# 06_MOV16_DestinationRegister.net
KiCad netlist of a schematic drawn in EAGLE
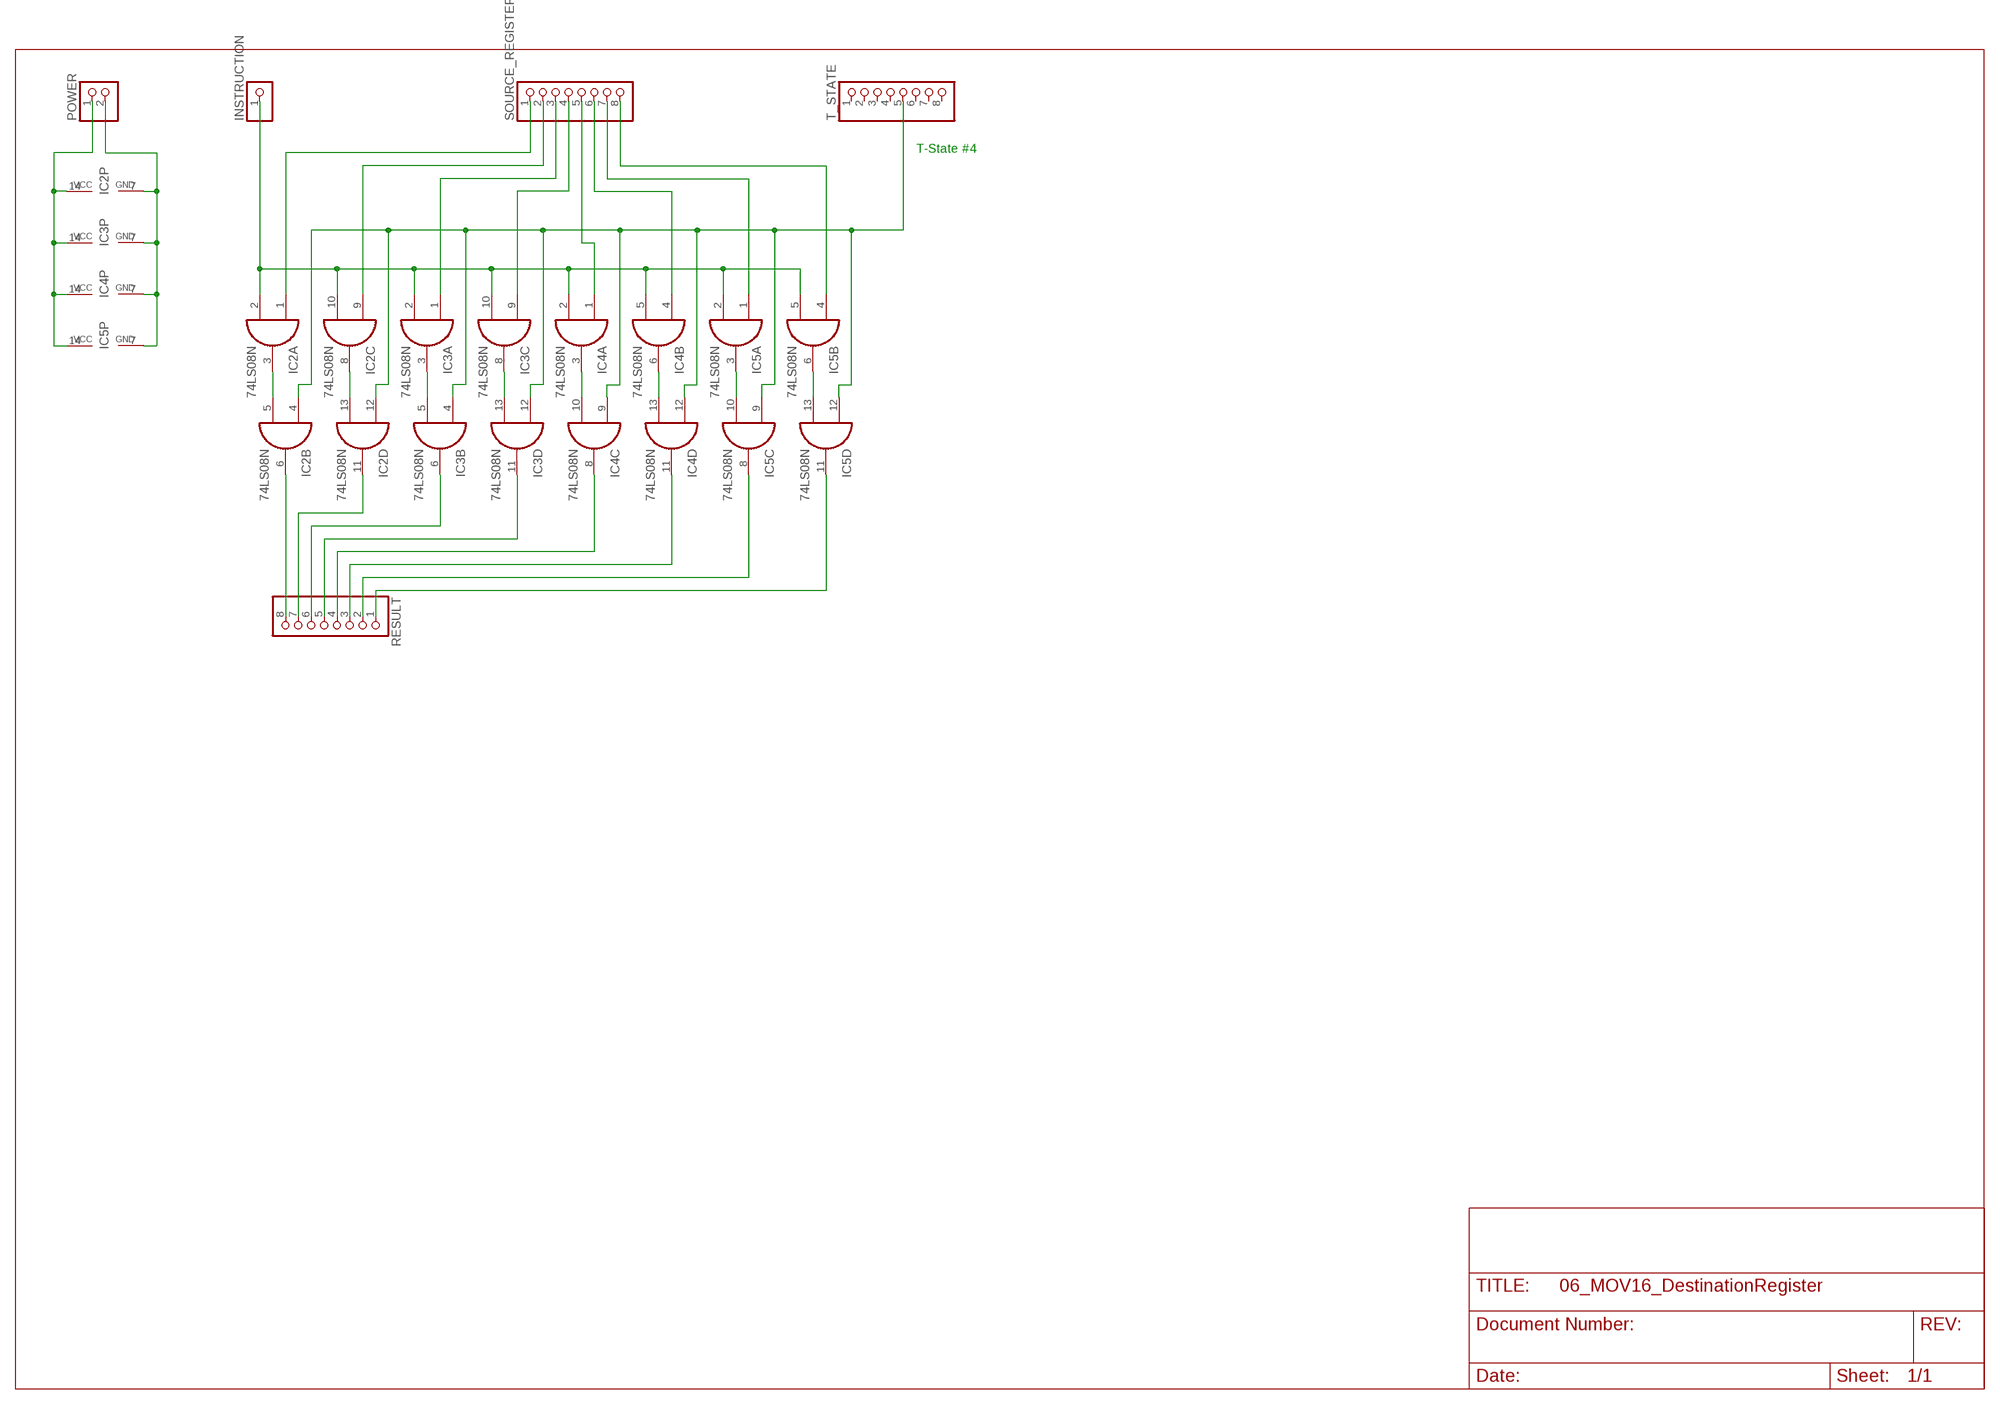
[diagram p0: schematic, sheet 1]

(export (version "E")
  (design (tool "Eeschema 10.0.6"))
  (components
    (comp (ref "IC2")
      (value "74LS08N")
      (footprint "eagle-import:DIL14")
      (libsource (lib "eagle-import") (part "7408NLS"))
    )
    (comp (ref "IC3")
      (value "74LS08N")
      (footprint "eagle-import:DIL14")
      (libsource (lib "eagle-import") (part "7408NLS"))
    )
    (comp (ref "IC4")
      (value "74LS08N")
      (footprint "eagle-import:DIL14")
      (libsource (lib "eagle-import") (part "7408NLS"))
    )
    (comp (ref "IC5")
      (value "74LS08N")
      (footprint "eagle-import:DIL14")
      (libsource (lib "eagle-import") (part "7408NLS"))
    )
    (comp (ref "INSTRUCTION")
      (value "PINHD-1X1")
      (footprint "eagle-import:1X01")
      (libsource (lib "eagle-import") (part "PINHD-1X1"))
    )
    (comp (ref "POWER")
      (value "PINHD-1X2")
      (footprint "eagle-import:1X02")
      (libsource (lib "eagle-import") (part "PINHD-1X2"))
    )
    (comp (ref "RESULT")
      (value "PINHD-1X8")
      (footprint "eagle-import:1X08")
      (libsource (lib "eagle-import") (part "PINHD-1X8"))
    )
    (comp (ref "SOURCE_REGISTER")
      (value "PINHD-1X8")
      (footprint "eagle-import:1X08")
      (libsource (lib "eagle-import") (part "PINHD-1X8"))
    )
    (comp (ref "T_STATE")
      (value "PINHD-1X8")
      (footprint "eagle-import:1X08")
      (libsource (lib "eagle-import") (part "PINHD-1X8"))
    )
  )
  (nets
    (net (code "1") (name "Net-(IC2A-I0)") (class "Default")
      (node (ref "IC2") (pin "1") (pinfunction "I0_1") (pintype "input"))
      (node (ref "SOURCE_REGISTER") (pin "1") (pinfunction "1_1") (pintype "passive"))
    )
    (net (code "2") (name "Net-(IC2A-I1)") (class "Default")
      (node (ref "IC2") (pin "10") (pinfunction "I1_10") (pintype "input"))
      (node (ref "IC2") (pin "2") (pinfunction "I1_2") (pintype "input"))
      (node (ref "IC3") (pin "10") (pinfunction "I1_10") (pintype "input"))
      (node (ref "IC3") (pin "2") (pinfunction "I1_2") (pintype "input"))
      (node (ref "IC4") (pin "2") (pinfunction "I1_2") (pintype "input"))
      (node (ref "IC4") (pin "5") (pinfunction "I1_5") (pintype "input"))
      (node (ref "IC5") (pin "2") (pinfunction "I1_2") (pintype "input"))
      (node (ref "IC5") (pin "5") (pinfunction "I1_5") (pintype "input"))
      (node (ref "INSTRUCTION") (pin "1") (pinfunction "1_1") (pintype "passive"))
    )
    (net (code "3") (name "Net-(IC2A-O)") (class "Default")
      (node (ref "IC2") (pin "3") (pinfunction "O_3") (pintype "output"))
      (node (ref "IC2") (pin "5") (pinfunction "I1_5") (pintype "input"))
    )
    (net (code "4") (name "Net-(IC2B-I0)") (class "Default")
      (node (ref "IC2") (pin "12") (pinfunction "I0_12") (pintype "input"))
      (node (ref "IC2") (pin "4") (pinfunction "I0_4") (pintype "input"))
      (node (ref "IC3") (pin "12") (pinfunction "I0_12") (pintype "input"))
      (node (ref "IC3") (pin "4") (pinfunction "I0_4") (pintype "input"))
      (node (ref "IC4") (pin "12") (pinfunction "I0_12") (pintype "input"))
      (node (ref "IC4") (pin "9") (pinfunction "I0_9") (pintype "input"))
      (node (ref "IC5") (pin "12") (pinfunction "I0_12") (pintype "input"))
      (node (ref "IC5") (pin "9") (pinfunction "I0_9") (pintype "input"))
      (node (ref "T_STATE") (pin "5") (pinfunction "5_5") (pintype "passive"))
    )
    (net (code "5") (name "Net-(IC2B-O)") (class "Default")
      (node (ref "IC2") (pin "6") (pinfunction "O_6") (pintype "output"))
      (node (ref "RESULT") (pin "8") (pinfunction "8_8") (pintype "passive"))
    )
    (net (code "6") (name "Net-(IC2C-I0)") (class "Default")
      (node (ref "IC2") (pin "9") (pinfunction "I0_9") (pintype "input"))
      (node (ref "SOURCE_REGISTER") (pin "2") (pinfunction "2_2") (pintype "passive"))
    )
    (net (code "7") (name "Net-(IC2C-O)") (class "Default")
      (node (ref "IC2") (pin "13") (pinfunction "I1_13") (pintype "input"))
      (node (ref "IC2") (pin "8") (pinfunction "O_8") (pintype "output"))
    )
    (net (code "8") (name "Net-(IC2D-O)") (class "Default")
      (node (ref "IC2") (pin "11") (pinfunction "O_11") (pintype "output"))
      (node (ref "RESULT") (pin "7") (pinfunction "7_7") (pintype "passive"))
    )
    (net (code "9") (name "Net-(IC2E-GND)") (class "Default")
      (node (ref "IC2") (pin "7") (pinfunction "GND_7") (pintype "power_in"))
      (node (ref "IC3") (pin "7") (pinfunction "GND_7") (pintype "power_in"))
      (node (ref "IC4") (pin "7") (pinfunction "GND_7") (pintype "power_in"))
      (node (ref "IC5") (pin "7") (pinfunction "GND_7") (pintype "power_in"))
      (node (ref "POWER") (pin "2") (pinfunction "2_2") (pintype "passive"))
    )
    (net (code "10") (name "Net-(IC2E-VCC)") (class "Default")
      (node (ref "IC2") (pin "14") (pinfunction "VCC_14") (pintype "power_in"))
      (node (ref "IC3") (pin "14") (pinfunction "VCC_14") (pintype "power_in"))
      (node (ref "IC4") (pin "14") (pinfunction "VCC_14") (pintype "power_in"))
      (node (ref "IC5") (pin "14") (pinfunction "VCC_14") (pintype "power_in"))
      (node (ref "POWER") (pin "1") (pinfunction "1_1") (pintype "passive"))
    )
    (net (code "11") (name "Net-(IC3A-I0)") (class "Default")
      (node (ref "IC3") (pin "1") (pinfunction "I0_1") (pintype "input"))
      (node (ref "SOURCE_REGISTER") (pin "3") (pinfunction "3_3") (pintype "passive"))
    )
    (net (code "12") (name "Net-(IC3A-O)") (class "Default")
      (node (ref "IC3") (pin "3") (pinfunction "O_3") (pintype "output"))
      (node (ref "IC3") (pin "5") (pinfunction "I1_5") (pintype "input"))
    )
    (net (code "13") (name "Net-(IC3B-O)") (class "Default")
      (node (ref "IC3") (pin "6") (pinfunction "O_6") (pintype "output"))
      (node (ref "RESULT") (pin "6") (pinfunction "6_6") (pintype "passive"))
    )
    (net (code "14") (name "Net-(IC3C-I0)") (class "Default")
      (node (ref "IC3") (pin "9") (pinfunction "I0_9") (pintype "input"))
      (node (ref "SOURCE_REGISTER") (pin "4") (pinfunction "4_4") (pintype "passive"))
    )
    (net (code "15") (name "Net-(IC3C-O)") (class "Default")
      (node (ref "IC3") (pin "13") (pinfunction "I1_13") (pintype "input"))
      (node (ref "IC3") (pin "8") (pinfunction "O_8") (pintype "output"))
    )
    (net (code "16") (name "Net-(IC3D-O)") (class "Default")
      (node (ref "IC3") (pin "11") (pinfunction "O_11") (pintype "output"))
      (node (ref "RESULT") (pin "5") (pinfunction "5_5") (pintype "passive"))
    )
    (net (code "17") (name "Net-(IC4A-I0)") (class "Default")
      (node (ref "IC4") (pin "1") (pinfunction "I0_1") (pintype "input"))
      (node (ref "SOURCE_REGISTER") (pin "5") (pinfunction "5_5") (pintype "passive"))
    )
    (net (code "18") (name "Net-(IC4A-O)") (class "Default")
      (node (ref "IC4") (pin "10") (pinfunction "I1_10") (pintype "input"))
      (node (ref "IC4") (pin "3") (pinfunction "O_3") (pintype "output"))
    )
    (net (code "19") (name "Net-(IC4B-I0)") (class "Default")
      (node (ref "IC4") (pin "4") (pinfunction "I0_4") (pintype "input"))
      (node (ref "SOURCE_REGISTER") (pin "6") (pinfunction "6_6") (pintype "passive"))
    )
    (net (code "20") (name "Net-(IC4B-O)") (class "Default")
      (node (ref "IC4") (pin "13") (pinfunction "I1_13") (pintype "input"))
      (node (ref "IC4") (pin "6") (pinfunction "O_6") (pintype "output"))
    )
    (net (code "21") (name "Net-(IC4C-O)") (class "Default")
      (node (ref "IC4") (pin "8") (pinfunction "O_8") (pintype "output"))
      (node (ref "RESULT") (pin "4") (pinfunction "4_4") (pintype "passive"))
    )
    (net (code "22") (name "Net-(IC4D-O)") (class "Default")
      (node (ref "IC4") (pin "11") (pinfunction "O_11") (pintype "output"))
      (node (ref "RESULT") (pin "3") (pinfunction "3_3") (pintype "passive"))
    )
    (net (code "23") (name "Net-(IC5A-I0)") (class "Default")
      (node (ref "IC5") (pin "1") (pinfunction "I0_1") (pintype "input"))
      (node (ref "SOURCE_REGISTER") (pin "7") (pinfunction "7_7") (pintype "passive"))
    )
    (net (code "24") (name "Net-(IC5A-O)") (class "Default")
      (node (ref "IC5") (pin "10") (pinfunction "I1_10") (pintype "input"))
      (node (ref "IC5") (pin "3") (pinfunction "O_3") (pintype "output"))
    )
    (net (code "25") (name "Net-(IC5B-I0)") (class "Default")
      (node (ref "IC5") (pin "4") (pinfunction "I0_4") (pintype "input"))
      (node (ref "SOURCE_REGISTER") (pin "8") (pinfunction "8_8") (pintype "passive"))
    )
    (net (code "26") (name "Net-(IC5B-O)") (class "Default")
      (node (ref "IC5") (pin "13") (pinfunction "I1_13") (pintype "input"))
      (node (ref "IC5") (pin "6") (pinfunction "O_6") (pintype "output"))
    )
    (net (code "27") (name "Net-(IC5C-O)") (class "Default")
      (node (ref "IC5") (pin "8") (pinfunction "O_8") (pintype "output"))
      (node (ref "RESULT") (pin "2") (pinfunction "2_2") (pintype "passive"))
    )
    (net (code "28") (name "Net-(IC5D-O)") (class "Default")
      (node (ref "IC5") (pin "11") (pinfunction "O_11") (pintype "output"))
      (node (ref "RESULT") (pin "1") (pinfunction "1_1") (pintype "passive"))
    )
    (net (code "29") (name "unconnected-(T_STATE-Pad1)") (class "Default")
      (node (ref "T_STATE") (pin "1") (pinfunction "1_1") (pintype "passive"))
    )
    (net (code "30") (name "unconnected-(T_STATE-Pad2)") (class "Default")
      (node (ref "T_STATE") (pin "2") (pinfunction "2_2") (pintype "passive"))
    )
    (net (code "31") (name "unconnected-(T_STATE-Pad3)") (class "Default")
      (node (ref "T_STATE") (pin "3") (pinfunction "3_3") (pintype "passive"))
    )
    (net (code "32") (name "unconnected-(T_STATE-Pad4)") (class "Default")
      (node (ref "T_STATE") (pin "4") (pinfunction "4_4") (pintype "passive"))
    )
    (net (code "33") (name "unconnected-(T_STATE-Pad6)") (class "Default")
      (node (ref "T_STATE") (pin "6") (pinfunction "6_6") (pintype "passive"))
    )
    (net (code "34") (name "unconnected-(T_STATE-Pad7)") (class "Default")
      (node (ref "T_STATE") (pin "7") (pinfunction "7_7") (pintype "passive"))
    )
    (net (code "35") (name "unconnected-(T_STATE-Pad8)") (class "Default")
      (node (ref "T_STATE") (pin "8") (pinfunction "8_8") (pintype "passive"))
    )
  )
)
